# ir-tara.net
KiCad netlist of a schematic drawn in Altium Designer
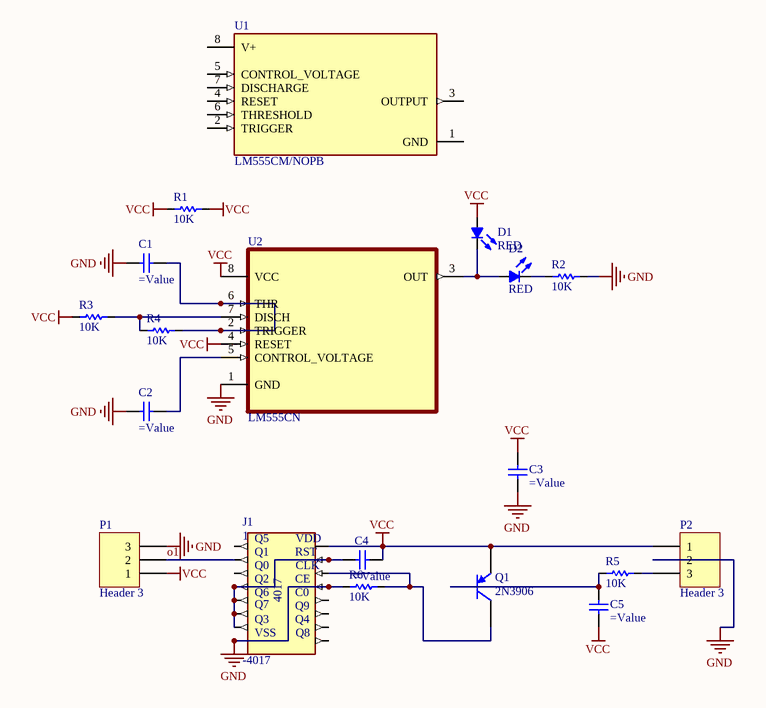
[diagram p0: ir-tara.SchDoc]

(export (version "E")
  (design (tool "Eeschema 10.0.6"))
  (components
    (comp (ref "C1")
      (value "~")
      (footprint "CAP 1206")
      (description "Capacitor")
      (libsource (lib "AltiumLib1") (part "Capacitor"))
    )
    (comp (ref "C2")
      (value "~")
      (footprint "CAP 1206")
      (description "Capacitor")
      (libsource (lib "AltiumLib1") (part "Capacitor"))
    )
    (comp (ref "C3")
      (value "~")
      (footprint "CAP 1206")
      (description "Capacitor")
      (libsource (lib "AltiumLib1") (part "Capacitor"))
    )
    (comp (ref "C4")
      (value "~")
      (footprint "CAP 1206")
      (description "Capacitor")
      (libsource (lib "AltiumLib1") (part "Capacitor"))
    )
    (comp (ref "C5")
      (value "~")
      (footprint "CAP 1206")
      (description "Capacitor")
      (libsource (lib "AltiumLib1") (part "Capacitor"))
    )
    (comp (ref "D1")
      (value "MODEL")
      (footprint "LED-5mm")
      (description "Typical LED")
      (fields (field (name "COLOR") "RED"))
      (libsource (lib "AltiumLib1") (part "LED 5mm"))
    )
    (comp (ref "D2")
      (value "MODEL")
      (footprint "LED-5mm")
      (description "Typical LED")
      (fields (field (name "COLOR") "RED"))
      (libsource (lib "AltiumLib1") (part "LED 5mm"))
    )
    (comp (ref "J1")
      (value "-4017")
      (footprint "DIL16")
      (description "10000pF Â±1% 25V Ceramic Capacitor C0G, NP0 0603 (1608 Metric)")
      (fields (field (name "MF") "Heyco") (field (name "MP") "4017"))
      (libsource (lib "-4017") (part "-4017"))
    )
    (comp (ref "P1")
      (value "Header 3")
      (footprint "HDR1X3")
      (description "Header, 3-Pin")
      (fields (field (name "PUBLISHER") "Altium Limited"))
      (libsource (lib "") (part "Header 3_1"))
    )
    (comp (ref "P2")
      (value "Header 3")
      (footprint "HDR1X3")
      (description "Header, 3-Pin")
      (fields (field (name "PUBLISHER") "Altium Limited"))
      (libsource (lib "Miscellaneous Connectors") (part "Header 3"))
    )
    (comp (ref "Q1")
      (value "2N3906")
      (footprint "MMBT3904-TP:SOT23-3")
      (description "PNP General Purpose Amplifier")
      (fields (field (name "PUBLISHER") "Altium Limited"))
      (libsource (lib "Miscellaneous Devices") (part "2N3906"))
    )
    (comp (ref "R1")
      (value "10K")
      (footprint "RES 1206 (3216X08L)")
      (description "Resistor")
      (fields (field (name "TOLERANCE") "5%") (field (name "POWER") "1/4 W"))
      (libsource (lib "AltiumLib1") (part "Resistor"))
    )
    (comp (ref "R2")
      (value "10K")
      (footprint "RES 1206 (3216X08L)")
      (description "Resistor")
      (fields (field (name "TOLERANCE") "5%") (field (name "POWER") "1/4 W"))
      (libsource (lib "AltiumLib1") (part "Resistor"))
    )
    (comp (ref "R3")
      (value "10K")
      (footprint "RES 1206 (3216X08L)")
      (description "Resistor")
      (fields (field (name "TOLERANCE") "5%") (field (name "POWER") "1/4 W"))
      (libsource (lib "AltiumLib1") (part "Resistor"))
    )
    (comp (ref "R4")
      (value "10K")
      (footprint "RES 1206 (3216X08L)")
      (description "Resistor")
      (fields (field (name "TOLERANCE") "5%") (field (name "POWER") "1/4 W"))
      (libsource (lib "AltiumLib1") (part "Resistor"))
    )
    (comp (ref "R5")
      (value "10K")
      (footprint "RES 1206 (3216X08L)")
      (description "Resistor")
      (fields (field (name "TOLERANCE") "5%") (field (name "POWER") "1/4 W"))
      (libsource (lib "AltiumLib1") (part "Resistor"))
    )
    (comp (ref "R6")
      (value "10K")
      (footprint "RES 1206 (3216X08L)")
      (description "Resistor")
      (fields (field (name "TOLERANCE") "5%") (field (name "POWER") "1/4 W"))
      (libsource (lib "AltiumLib1") (part "Resistor"))
    )
    (comp (ref "U1")
      (value "LM555CM/NOPB")
      (footprint "SOIC127P599X175-8N")
      (description "Highly Stable 555 Timer 8-SOIC 0 to 70")
      (libsource (lib "LM555CM_NOPB") (part "LM555CM/NOPB"))
    )
    (comp (ref "U2")
      (value "LM555CN")
      (footprint "DIP254P762X533-8")
      (description "555 Type, Timer/Oscillator _Single_ IC 100kHz 8-PDIP")
      (fields (field (name "MF") "Texas Instruments"))
      (libsource (lib "LM555CN") (part "LM555CN"))
    )
  )
  (nets
    (net (code "1") (name "/o1") (class "Default")
      (node (ref "J1") (pin "2") (pinfunction "Q1_2") (pintype "output"))
      (node (ref "P1") (pin "2") (pinfunction "2_2") (pintype "passive"))
    )
    (net (code "2") (name "GND") (class "Default")
      (node (ref "C1") (pin "2") (pinfunction "-_2") (pintype "passive"))
      (node (ref "C2") (pin "2") (pinfunction "-_2") (pintype "passive"))
      (node (ref "C3") (pin "2") (pinfunction "-_2") (pintype "passive"))
      (node (ref "J1") (pin "13") (pinfunction "CE_13") (pintype "input"))
      (node (ref "J1") (pin "8") (pinfunction "VSS_8") (pintype "power_in"))
      (node (ref "P1") (pin "3") (pinfunction "3_3") (pintype "passive"))
      (node (ref "P2") (pin "2") (pinfunction "2_2") (pintype "passive"))
      (node (ref "R2") (pin "2") (pinfunction "2_2") (pintype "passive"))
      (node (ref "R6") (pin "2") (pinfunction "2_2") (pintype "passive"))
      (node (ref "U2") (pin "1") (pinfunction "GND_1") (pintype "passive"))
    )
    (net (code "3") (name "Net-(C1-+)") (class "Default")
      (node (ref "C1") (pin "1") (pinfunction "+_1") (pintype "passive"))
      (node (ref "R4") (pin "1") (pinfunction "1_1") (pintype "passive"))
      (node (ref "U2") (pin "2") (pinfunction "TRIGGER_2") (pintype "input"))
      (node (ref "U2") (pin "6") (pinfunction "THR_6") (pintype "input"))
    )
    (net (code "4") (name "Net-(C2-+)") (class "Default")
      (node (ref "C2") (pin "1") (pinfunction "+_1") (pintype "passive"))
      (node (ref "U2") (pin "5") (pinfunction "CONTROL_VOLTAGE_5") (pintype "input"))
    )
    (net (code "5") (name "Net-(C4--)") (class "Default")
      (node (ref "C4") (pin "2") (pinfunction "-_2") (pintype "passive"))
      (node (ref "J1") (pin "15") (pinfunction "RST_15") (pintype "input"))
      (node (ref "J1") (pin "4") (pinfunction "Q2_4") (pintype "output"))
      (node (ref "J1") (pin "5") (pinfunction "Q6_5") (pintype "output"))
      (node (ref "J1") (pin "6") (pinfunction "Q7_6") (pintype "output"))
      (node (ref "J1") (pin "7") (pinfunction "Q3_7") (pintype "output"))
    )
    (net (code "6") (name "Net-(C5-+)") (class "Default")
      (node (ref "C5") (pin "1") (pinfunction "+_1") (pintype "passive"))
      (node (ref "Q1") (pin "2") (pinfunction "B_2") (pintype "passive"))
      (node (ref "R5") (pin "2") (pinfunction "2_2") (pintype "passive"))
    )
    (net (code "7") (name "Net-(D1-K)") (class "Default")
      (node (ref "D1") (pin "2") (pinfunction "K_2") (pintype "passive"))
      (node (ref "D2") (pin "1") (pinfunction "A_1") (pintype "passive"))
      (node (ref "U2") (pin "3") (pinfunction "OUT_3") (pintype "output"))
    )
    (net (code "8") (name "Net-(D2-K)") (class "Default")
      (node (ref "D2") (pin "2") (pinfunction "K_2") (pintype "passive"))
      (node (ref "R2") (pin "1") (pinfunction "1_1") (pintype "passive"))
    )
    (net (code "9") (name "Net-(J1-CLK)") (class "Default")
      (node (ref "J1") (pin "14") (pinfunction "CLK_14") (pintype "input"))
      (node (ref "Q1") (pin "3") (pinfunction "C_3") (pintype "passive"))
      (node (ref "R6") (pin "1") (pinfunction "1_1") (pintype "passive"))
    )
    (net (code "10") (name "Net-(P2-Pad3)") (class "Default")
      (node (ref "P2") (pin "3") (pinfunction "3_3") (pintype "passive"))
      (node (ref "R5") (pin "1") (pinfunction "1_1") (pintype "passive"))
    )
    (net (code "11") (name "Net-(U2-DISCH)") (class "Default")
      (node (ref "R3") (pin "1") (pinfunction "1_1") (pintype "passive"))
      (node (ref "R4") (pin "2") (pinfunction "2_2") (pintype "passive"))
      (node (ref "U2") (pin "7") (pinfunction "DISCH_7") (pintype "input"))
    )
    (net (code "12") (name "VCC") (class "Default")
      (node (ref "C3") (pin "1") (pinfunction "+_1") (pintype "passive"))
      (node (ref "C4") (pin "1") (pinfunction "+_1") (pintype "passive"))
      (node (ref "C5") (pin "2") (pinfunction "-_2") (pintype "passive"))
      (node (ref "D1") (pin "1") (pinfunction "A_1") (pintype "passive"))
      (node (ref "J1") (pin "16") (pinfunction "VDD_16") (pintype "power_in"))
      (node (ref "P1") (pin "1") (pinfunction "1_1") (pintype "passive"))
      (node (ref "P2") (pin "1") (pinfunction "1_1") (pintype "passive"))
      (node (ref "Q1") (pin "1") (pinfunction "E_1") (pintype "passive"))
      (node (ref "R1") (pin "1") (pinfunction "1_1") (pintype "passive"))
      (node (ref "R1") (pin "2") (pinfunction "2_2") (pintype "passive"))
      (node (ref "R3") (pin "2") (pinfunction "2_2") (pintype "passive"))
      (node (ref "U2") (pin "4") (pinfunction "RESET_4") (pintype "input"))
      (node (ref "U2") (pin "8") (pinfunction "VCC_8") (pintype "power_in"))
    )
    (net (code "13") (name "unconnected-(J1-C0-Pad12)") (class "Default")
      (node (ref "J1") (pin "12") (pinfunction "C0_12") (pintype "output"))
    )
    (net (code "14") (name "unconnected-(J1-Q0-Pad3)") (class "Default")
      (node (ref "J1") (pin "3") (pinfunction "Q0_3") (pintype "output"))
    )
    (net (code "15") (name "unconnected-(J1-Q4-Pad10)") (class "Default")
      (node (ref "J1") (pin "10") (pinfunction "Q4_10") (pintype "output"))
    )
    (net (code "16") (name "unconnected-(J1-Q5-Pad1)") (class "Default")
      (node (ref "J1") (pin "1") (pinfunction "Q5_1") (pintype "output"))
    )
    (net (code "17") (name "unconnected-(J1-Q8-Pad9)") (class "Default")
      (node (ref "J1") (pin "9") (pinfunction "Q8_9") (pintype "output"))
    )
    (net (code "18") (name "unconnected-(J1-Q9-Pad11)") (class "Default")
      (node (ref "J1") (pin "11") (pinfunction "Q9_11") (pintype "output"))
    )
    (net (code "19") (name "unconnected-(U1-CONTROL_VOLTAGE-Pad5)") (class "Default")
      (node (ref "U1") (pin "5") (pinfunction "CONTROL_VOLTAGE_5") (pintype "input"))
    )
    (net (code "20") (name "unconnected-(U1-DISCHARGE-Pad7)") (class "Default")
      (node (ref "U1") (pin "7") (pinfunction "DISCHARGE_7") (pintype "input"))
    )
    (net (code "21") (name "unconnected-(U1-GND-Pad1)") (class "Default")
      (node (ref "U1") (pin "1") (pinfunction "GND_1") (pintype "power_in"))
    )
    (net (code "22") (name "unconnected-(U1-OUTPUT-Pad3)") (class "Default")
      (node (ref "U1") (pin "3") (pinfunction "OUTPUT_3") (pintype "output"))
    )
    (net (code "23") (name "unconnected-(U1-RESET-Pad4)") (class "Default")
      (node (ref "U1") (pin "4") (pinfunction "RESET_4") (pintype "input"))
    )
    (net (code "24") (name "unconnected-(U1-THRESHOLD-Pad6)") (class "Default")
      (node (ref "U1") (pin "6") (pinfunction "THRESHOLD_6") (pintype "input"))
    )
    (net (code "25") (name "unconnected-(U1-TRIGGER-Pad2)") (class "Default")
      (node (ref "U1") (pin "2") (pinfunction "TRIGGER_2") (pintype "input"))
    )
    (net (code "26") (name "unconnected-(U1-V+-Pad8)") (class "Default")
      (node (ref "U1") (pin "8") (pinfunction "V+_8") (pintype "power_in"))
    )
  )
)
